# TestBoard3.net
KiCad netlist of a schematic drawn in EAGLE
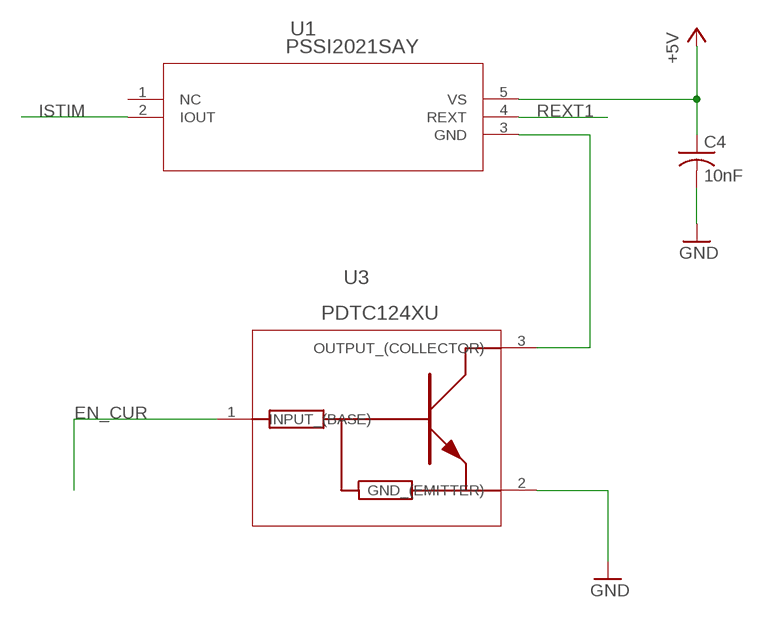
[diagram p0: schematic, sheet 1]
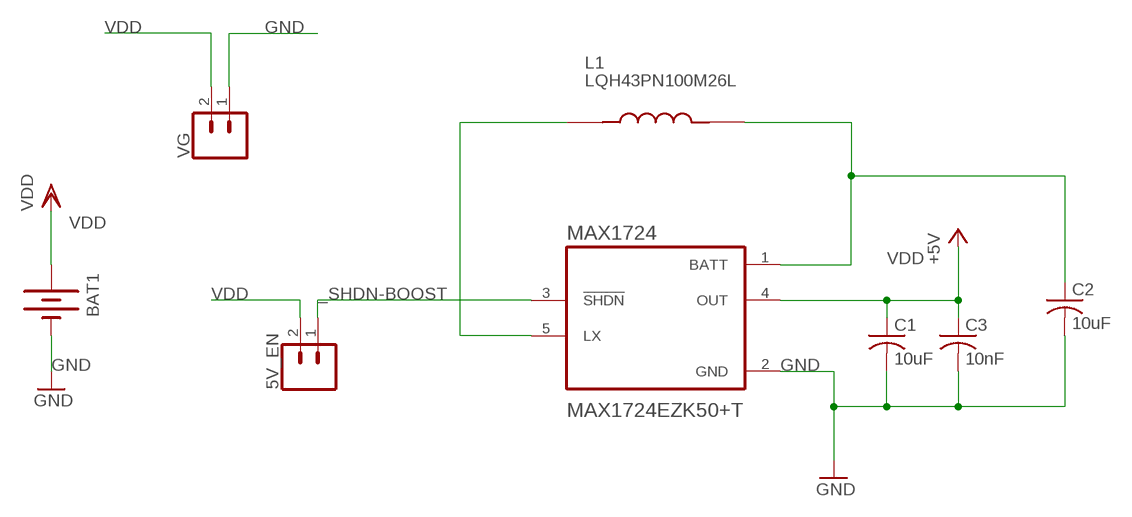
[diagram p1: schematic, sheet 2]
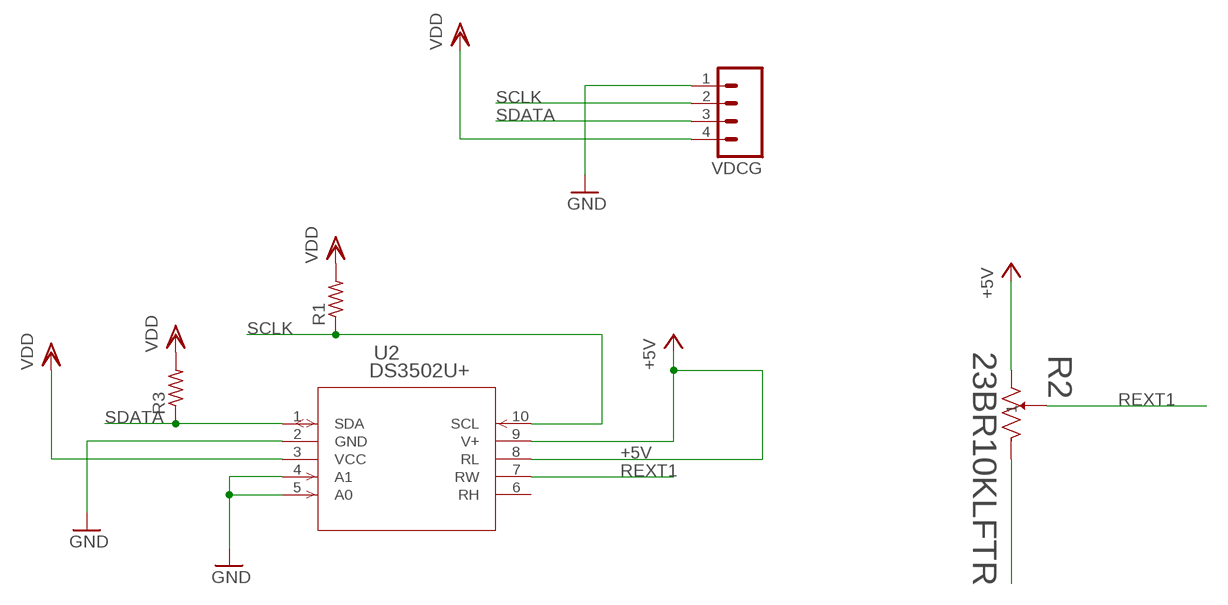
[diagram p2: schematic, sheet 3]
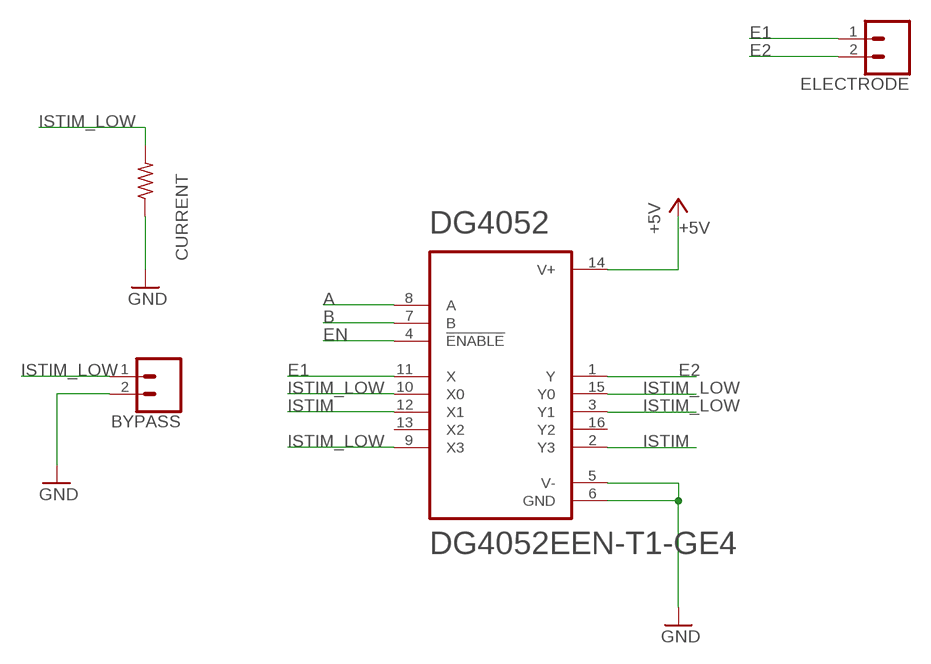
[diagram p3: schematic, sheet 4]
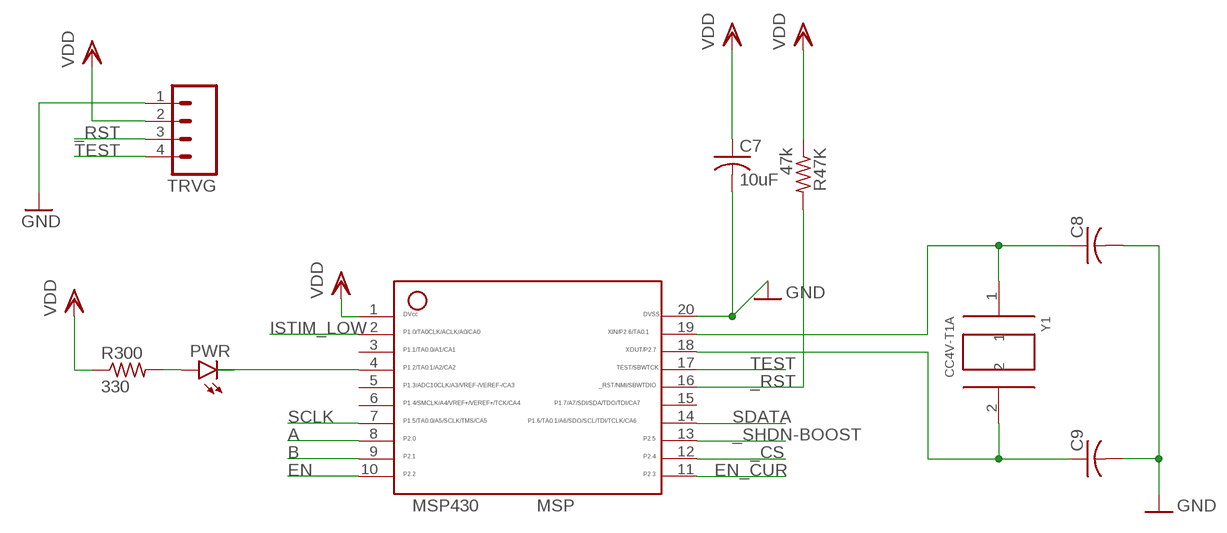
[diagram p4: schematic, sheet 5]

(export (version "E")
  (design (tool "Eeschema 10.0.6"))
  (components
    (comp (ref "R1")
      (value "R-US_R0603")
      (footprint "eagle-import:R0603")
      (libsource (lib "eagle-import") (part "R-US_R0603"))
    )
    (comp (ref "R2")
      (value "23BR10KLFTR")
      (footprint "eagle-import:RES3_23B_TTE")
      (fields (field (name "COPYRIGHT") "Copyright (C) 2016 Accelerated Designs. All rights reserved"))
      (libsource (lib "eagle-import") (part "23BR10KLFTR"))
    )
    (comp (ref "R3")
      (value "R-US_R0603")
      (footprint "eagle-import:R0603")
      (libsource (lib "eagle-import") (part "R-US_R0603"))
    )
    (comp (ref "U2")
      (value "DS3502U+")
      (footprint "eagle-import:21-0061_U10+2_MXM")
      (fields
        (field (name "MANUFACTURER_PART_NUMBER") "ds3502u+")
        (field (name "COPYRIGHT") "Copyright (C) 2022 Ultra Librarian. All rights reserved.")
      )
      (libsource (lib "eagle-import") (part "DS3502U+"))
    )
    (comp (ref "VDCG")
      (value "M04LOCK")
      (footprint "eagle-import:1X04_LOCK")
      (libsource (lib "eagle-import") (part "M04LOCK"))
    )
    (comp (ref "C4")
      (value "10nF")
      (footprint "eagle-import:C0603")
      (libsource (lib "eagle-import") (part "C-USC0603"))
    )
    (comp (ref "U1")
      (value "PSSI2021SAY")
      (footprint "eagle-import:SOT353_NXP")
      (fields (field (name "COPYRIGHT") "Copyright (C) 2021 Ultra Librarian. All rights reserved."))
      (libsource (lib "eagle-import") (part "PSSI2021SAY"))
    )
    (comp (ref "U3")
      (value "PDTC124XU")
      (footprint "eagle-import:SOT323_NXP")
      (fields (field (name "COPYRIGHT") "Copyright (C) 2021 Ultra Librarian. All rights reserved."))
      (libsource (lib "eagle-import") (part "PDTC124XU"))
    )
    (comp (ref "BYPASS")
      (value "CONN_02LOCK")
      (footprint "eagle-import:1X02_LOCK")
      (libsource (lib "eagle-import") (part "CONN_02LOCK"))
    )
    (comp (ref "CURRENT")
      (value "R-US_0204/7")
      (footprint "eagle-import:0204_7")
      (libsource (lib "eagle-import") (part "R-US_0204/7"))
    )
    (comp (ref "DG4052")
      (value "DG4052EEN-T1-GE4")
      (footprint "eagle-import:QFN40P260X180X60-16N")
      (fields (field (name "DIGI-KEY_PART_NUMBER") "DG4052EEN-T1-GE4CT-ND") (field (name "MF") "Vishay"))
      (libsource (lib "eagle-import") (part "DG4052EEN-T1-GE4"))
    )
    (comp (ref "ELECTRODE")
      (value "CONN_02")
      (footprint "eagle-import:1X02")
      (libsource (lib "eagle-import") (part "CONN_02"))
    )
    (comp (ref "5V_EN")
      (value "CONN_02")
      (footprint "eagle-import:1X02")
      (libsource (lib "eagle-import") (part "CONN_02"))
    )
    (comp (ref "BAT1")
      (value "BATTERYBU2032SM")
      (footprint "eagle-import:BU2032SM")
      (libsource (lib "eagle-import") (part "BATTERYBU2032SM"))
    )
    (comp (ref "C1")
      (value "10uF")
      (footprint "eagle-import:C1206")
      (libsource (lib "eagle-import") (part "C-USC1206"))
    )
    (comp (ref "C2")
      (value "10uF")
      (footprint "eagle-import:C1206")
      (libsource (lib "eagle-import") (part "C-USC1206"))
    )
    (comp (ref "C3")
      (value "10nF")
      (footprint "eagle-import:C0603")
      (libsource (lib "eagle-import") (part "C-USC0603"))
    )
    (comp (ref "L1")
      (value "LQH43PN100M26L")
      (footprint "eagle-import:IND_LQH43PN100M26L")
      (fields (field (name "DIGI-KEY_PART_NUMBER") "490-12780-1-ND") (field (name "MF") "Murata"))
      (libsource (lib "eagle-import") (part "LQH43PN100M26L"))
    )
    (comp (ref "MAX1724")
      (value "MAX1724EZK50+T")
      (footprint "eagle-import:SOT95P275X110-5N")
      (fields
        (field (name "DIGI-KEY_PART_NUMBER") "MAX1724EZK50+TCT-ND")
        (field (name "MF") "Maxim Integrated")
      )
      (libsource (lib "eagle-import") (part "MAX1724EZK50+T"))
    )
    (comp (ref "VG")
      (value "CONN_02")
      (footprint "eagle-import:1X02")
      (libsource (lib "eagle-import") (part "CONN_02"))
    )
    (comp (ref "C7")
      (value "10uF")
      (footprint "eagle-import:C1206")
      (libsource (lib "eagle-import") (part "C-USC1206"))
    )
    (comp (ref "C8")
      (value "C-USC0603")
      (footprint "eagle-import:C0603")
      (libsource (lib "eagle-import") (part "C-USC0603"))
    )
    (comp (ref "C9")
      (value "C-USC0603")
      (footprint "eagle-import:C0603")
      (libsource (lib "eagle-import") (part "C-USC0603"))
    )
    (comp (ref "MSP430")
      (value "MSP")
      (footprint "eagle-import:20_PIN")
      (libsource (lib "eagle-import") (part "MSP430"))
    )
    (comp (ref "PWR")
      (value "LEDCHIPLED_0603")
      (footprint "eagle-import:CHIPLED_0603")
      (libsource (lib "eagle-import") (part "LEDCHIPLED_0603"))
    )
    (comp (ref "R47K")
      (value "47k")
      (footprint "eagle-import:R0603")
      (libsource (lib "eagle-import") (part "R-US_R0603"))
    )
    (comp (ref "R300")
      (value "330")
      (footprint "eagle-import:R0603")
      (libsource (lib "eagle-import") (part "R-US_R0603"))
    )
    (comp (ref "TRVG")
      (value "M04LOCK")
      (footprint "eagle-import:1X04_LOCK")
      (libsource (lib "eagle-import") (part "M04LOCK"))
    )
    (comp (ref "Y1")
      (value "CC4V-T1A")
      (footprint "eagle-import:CC4V-T1A")
      (fields (field (name "MF") "Micro Crystal AG") (field (name "MP") "CC4V-T1A-32.768KHZ-7PF-20PPM"))
      (libsource (lib "eagle-import") (part "CC4V-T1A"))
    )
  )
  (nets
    (net (code "1") (name "+5V") (class "Default")
      (node (ref "C1") (pin "1") (pinfunction "1_1") (pintype "passive"))
      (node (ref "C3") (pin "1") (pinfunction "1_1") (pintype "passive"))
      (node (ref "C4") (pin "1") (pinfunction "1_1") (pintype "passive"))
      (node (ref "DG4052") (pin "14") (pinfunction "V+_14") (pintype "power_in"))
      (node (ref "MAX1724") (pin "4") (pinfunction "OUT_4") (pintype "output"))
      (node (ref "R2") (pin "1") (pinfunction "1_1") (pintype "passive"))
      (node (ref "U1") (pin "5") (pinfunction "VS_5") (pintype "passive"))
      (node (ref "U2") (pin "8") (pinfunction "RL_8") (pintype "passive"))
      (node (ref "U2") (pin "9") (pinfunction "V+_9") (pintype "power_in"))
    )
    (net (code "2") (name "A") (class "Default")
      (node (ref "DG4052") (pin "8") (pinfunction "A_8") (pintype "input"))
      (node (ref "MSP430") (pin "8") (pinfunction "8_8") (pintype "bidirectional"))
    )
    (net (code "3") (name "B") (class "Default")
      (node (ref "DG4052") (pin "7") (pinfunction "B_7") (pintype "input"))
      (node (ref "MSP430") (pin "9") (pinfunction "9_9") (pintype "bidirectional"))
    )
    (net (code "4") (name "E1") (class "Default")
      (node (ref "DG4052") (pin "11") (pinfunction "X_11") (pintype "passive"))
      (node (ref "ELECTRODE") (pin "1") (pinfunction "1_1") (pintype "passive"))
    )
    (net (code "5") (name "E2") (class "Default")
      (node (ref "DG4052") (pin "1") (pinfunction "Y_1") (pintype "passive"))
      (node (ref "ELECTRODE") (pin "2") (pinfunction "2_2") (pintype "passive"))
    )
    (net (code "6") (name "EN") (class "Default")
      (node (ref "DG4052") (pin "4") (pinfunction "~{ENABLE}_4") (pintype "input"))
      (node (ref "MSP430") (pin "10") (pinfunction "10_10") (pintype "bidirectional"))
    )
    (net (code "7") (name "EN_CUR") (class "Default")
      (node (ref "MSP430") (pin "11") (pinfunction "11_11") (pintype "bidirectional"))
      (node (ref "U3") (pin "1") (pinfunction "INPUT_(BASE)_1") (pintype "passive"))
    )
    (net (code "8") (name "GND") (class "Default")
      (node (ref "BAT1") (pin "P$2") (pinfunction "-_P$2") (pintype "power_in"))
      (node (ref "BYPASS") (pin "2") (pinfunction "2_2") (pintype "passive"))
      (node (ref "C1") (pin "2") (pinfunction "2_2") (pintype "passive"))
      (node (ref "C2") (pin "2") (pinfunction "2_2") (pintype "passive"))
      (node (ref "C3") (pin "2") (pinfunction "2_2") (pintype "passive"))
      (node (ref "C4") (pin "2") (pinfunction "2_2") (pintype "passive"))
      (node (ref "C7") (pin "2") (pinfunction "2_2") (pintype "passive"))
      (node (ref "C8") (pin "2") (pinfunction "2_2") (pintype "passive"))
      (node (ref "C9") (pin "2") (pinfunction "2_2") (pintype "passive"))
      (node (ref "CURRENT") (pin "1") (pinfunction "1_1") (pintype "passive"))
      (node (ref "DG4052") (pin "5") (pinfunction "V-_5") (pintype "power_in"))
      (node (ref "DG4052") (pin "6") (pinfunction "GND_6") (pintype "power_in"))
      (node (ref "MAX1724") (pin "2") (pinfunction "GND_2") (pintype "power_in"))
      (node (ref "MSP430") (pin "20") (pinfunction "20_20") (pintype "bidirectional"))
      (node (ref "TRVG") (pin "1") (pinfunction "1_1") (pintype "passive"))
      (node (ref "U2") (pin "2") (pinfunction "GND_2") (pintype "power_in"))
      (node (ref "U2") (pin "4") (pinfunction "A1_4") (pintype "input"))
      (node (ref "U2") (pin "5") (pinfunction "A0_5") (pintype "input"))
      (node (ref "U3") (pin "2") (pinfunction "GND_(EMITTER)_2") (pintype "passive"))
      (node (ref "VDCG") (pin "1") (pinfunction "1_1") (pintype "passive"))
      (node (ref "VG") (pin "1") (pinfunction "1_1") (pintype "passive"))
    )
    (net (code "9") (name "ISTIM") (class "Default")
      (node (ref "DG4052") (pin "12") (pinfunction "X1_12") (pintype "passive"))
      (node (ref "DG4052") (pin "2") (pinfunction "Y3_2") (pintype "passive"))
      (node (ref "U1") (pin "2") (pinfunction "IOUT_2") (pintype "passive"))
    )
    (net (code "10") (name "ISTIM_LOW") (class "Default")
      (node (ref "BYPASS") (pin "1") (pinfunction "1_1") (pintype "passive"))
      (node (ref "CURRENT") (pin "2") (pinfunction "2_2") (pintype "passive"))
      (node (ref "DG4052") (pin "10") (pinfunction "X0_10") (pintype "passive"))
      (node (ref "DG4052") (pin "15") (pinfunction "Y0_15") (pintype "passive"))
      (node (ref "DG4052") (pin "3") (pinfunction "Y1_3") (pintype "passive"))
      (node (ref "DG4052") (pin "9") (pinfunction "X3_9") (pintype "passive"))
      (node (ref "MSP430") (pin "2") (pinfunction "2_2") (pintype "bidirectional"))
    )
    (net (code "11") (name "Net-(C8-Pad1)") (class "Default")
      (node (ref "C8") (pin "1") (pinfunction "1_1") (pintype "passive"))
      (node (ref "MSP430") (pin "19") (pinfunction "19_19") (pintype "bidirectional"))
      (node (ref "Y1") (pin "1") (pinfunction "1_1") (pintype "passive"))
    )
    (net (code "12") (name "Net-(C9-Pad1)") (class "Default")
      (node (ref "C9") (pin "1") (pinfunction "1_1") (pintype "passive"))
      (node (ref "MSP430") (pin "18") (pinfunction "18_18") (pintype "bidirectional"))
      (node (ref "Y1") (pin "2") (pinfunction "2_2") (pintype "passive"))
    )
    (net (code "13") (name "Net-(MAX1724-LX)") (class "Default")
      (node (ref "L1") (pin "1") (pinfunction "1_1") (pintype "passive"))
      (node (ref "MAX1724") (pin "5") (pinfunction "LX_5") (pintype "bidirectional"))
    )
    (net (code "14") (name "Net-(MSP430-Pad4)") (class "Default")
      (node (ref "MSP430") (pin "4") (pinfunction "4_4") (pintype "bidirectional"))
      (node (ref "PWR") (pin "C") (pinfunction "C_C") (pintype "passive"))
    )
    (net (code "15") (name "Net-(PWR-PadA)") (class "Default")
      (node (ref "PWR") (pin "A") (pinfunction "A_A") (pintype "passive"))
      (node (ref "R300") (pin "2") (pinfunction "2_2") (pintype "passive"))
    )
    (net (code "16") (name "Net-(U1-GND)") (class "Default")
      (node (ref "U1") (pin "3") (pinfunction "GND_3") (pintype "passive"))
      (node (ref "U3") (pin "3") (pinfunction "OUTPUT_(COLLECTOR)_3") (pintype "passive"))
    )
    (net (code "17") (name "REXT1") (class "Default")
      (node (ref "R2") (pin "2") (pinfunction "2_2") (pintype "passive"))
      (node (ref "U1") (pin "4") (pinfunction "REXT_4") (pintype "passive"))
      (node (ref "U2") (pin "7") (pinfunction "RW_7") (pintype "passive"))
    )
    (net (code "18") (name "SCLK") (class "Default")
      (node (ref "MSP430") (pin "7") (pinfunction "7_7") (pintype "bidirectional"))
      (node (ref "R1") (pin "1") (pinfunction "1_1") (pintype "passive"))
      (node (ref "U2") (pin "10") (pinfunction "SCL_10") (pintype "input"))
      (node (ref "VDCG") (pin "2") (pinfunction "2_2") (pintype "passive"))
    )
    (net (code "19") (name "SDATA") (class "Default")
      (node (ref "MSP430") (pin "14") (pinfunction "14_14") (pintype "bidirectional"))
      (node (ref "R3") (pin "1") (pinfunction "1_1") (pintype "passive"))
      (node (ref "U2") (pin "1") (pinfunction "SDA_1") (pintype "bidirectional"))
      (node (ref "VDCG") (pin "3") (pinfunction "3_3") (pintype "passive"))
    )
    (net (code "20") (name "TEST") (class "Default")
      (node (ref "MSP430") (pin "17") (pinfunction "17_17") (pintype "bidirectional"))
      (node (ref "TRVG") (pin "4") (pinfunction "4_4") (pintype "passive"))
    )
    (net (code "21") (name "VDD") (class "Default")
      (node (ref "5V_EN") (pin "2") (pinfunction "2_2") (pintype "passive"))
      (node (ref "BAT1") (pin "P$1") (pinfunction "+_P$1") (pintype "power_in"))
      (node (ref "C2") (pin "1") (pinfunction "1_1") (pintype "passive"))
      (node (ref "C7") (pin "1") (pinfunction "1_1") (pintype "passive"))
      (node (ref "L1") (pin "2") (pinfunction "2_2") (pintype "passive"))
      (node (ref "MAX1724") (pin "1") (pinfunction "BATT_1") (pintype "power_in"))
      (node (ref "MSP430") (pin "1") (pinfunction "1_1") (pintype "bidirectional"))
      (node (ref "R1") (pin "2") (pinfunction "2_2") (pintype "passive"))
      (node (ref "R3") (pin "2") (pinfunction "2_2") (pintype "passive"))
      (node (ref "R300") (pin "1") (pinfunction "1_1") (pintype "passive"))
      (node (ref "R47K") (pin "1") (pinfunction "1_1") (pintype "passive"))
      (node (ref "TRVG") (pin "2") (pinfunction "2_2") (pintype "passive"))
      (node (ref "U2") (pin "3") (pinfunction "VCC_3") (pintype "power_in"))
      (node (ref "VDCG") (pin "4") (pinfunction "4_4") (pintype "passive"))
      (node (ref "VG") (pin "2") (pinfunction "2_2") (pintype "passive"))
    )
    (net (code "22") (name "_CS") (class "Default")
      (node (ref "MSP430") (pin "12") (pinfunction "12_12") (pintype "bidirectional"))
    )
    (net (code "23") (name "_RST") (class "Default")
      (node (ref "MSP430") (pin "16") (pinfunction "16_16") (pintype "bidirectional"))
      (node (ref "R47K") (pin "2") (pinfunction "2_2") (pintype "passive"))
      (node (ref "TRVG") (pin "3") (pinfunction "3_3") (pintype "passive"))
    )
    (net (code "24") (name "_SHDN-BOOST") (class "Default")
      (node (ref "5V_EN") (pin "1") (pinfunction "1_1") (pintype "passive"))
      (node (ref "MAX1724") (pin "3") (pinfunction "~{SHDN}_3") (pintype "input"))
      (node (ref "MSP430") (pin "13") (pinfunction "13_13") (pintype "bidirectional"))
    )
    (net (code "25") (name "unconnected-(DG4052-X2-Pad13)") (class "Default")
      (node (ref "DG4052") (pin "13") (pinfunction "X2_13") (pintype "passive"))
    )
    (net (code "26") (name "unconnected-(DG4052-Y2-Pad16)") (class "Default")
      (node (ref "DG4052") (pin "16") (pinfunction "Y2_16") (pintype "passive"))
    )
    (net (code "27") (name "unconnected-(MSP430-Pad3)") (class "Default")
      (node (ref "MSP430") (pin "3") (pinfunction "3_3") (pintype "bidirectional"))
    )
    (net (code "28") (name "unconnected-(MSP430-Pad5)") (class "Default")
      (node (ref "MSP430") (pin "5") (pinfunction "5_5") (pintype "bidirectional"))
    )
    (net (code "29") (name "unconnected-(MSP430-Pad6)") (class "Default")
      (node (ref "MSP430") (pin "6") (pinfunction "6_6") (pintype "bidirectional"))
    )
    (net (code "30") (name "unconnected-(MSP430-Pad15)") (class "Default")
      (node (ref "MSP430") (pin "15") (pinfunction "15_15") (pintype "bidirectional"))
    )
    (net (code "31") (name "unconnected-(R2-Pad3)") (class "Default")
      (node (ref "R2") (pin "3") (pinfunction "3_3") (pintype "passive"))
    )
    (net (code "32") (name "unconnected-(U1-NC-Pad1)") (class "Default")
      (node (ref "U1") (pin "1") (pinfunction "NC_1") (pintype "passive"))
    )
    (net (code "33") (name "unconnected-(U2-RH-Pad6)") (class "Default")
      (node (ref "U2") (pin "6") (pinfunction "RH_6") (pintype "passive"))
    )
  )
)
